# atxmega16d4.net
KiCad netlist of a schematic drawn in EAGLE
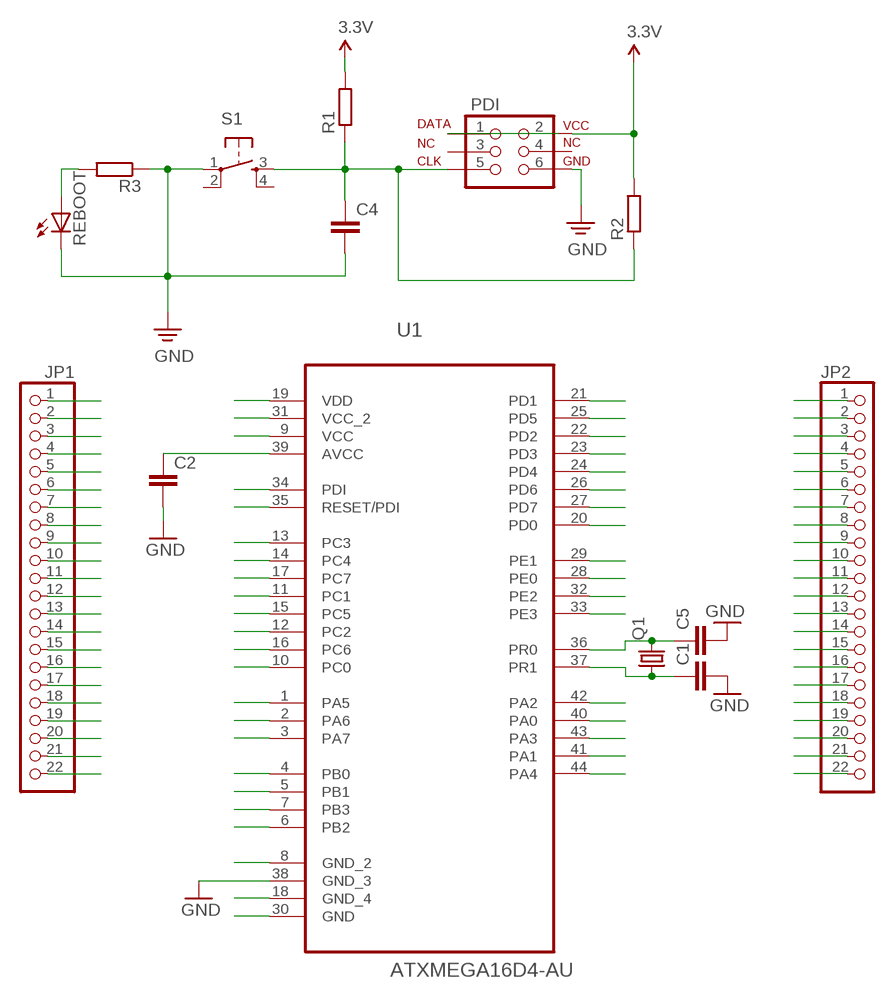
[diagram p0: schematic, sheet 1]

(export (version "E")
  (design (tool "Eeschema 10.0.6"))
  (components
    (comp (ref "C1")
      (value "C-EU025-025X050")
      (footprint "eagle-import:C025-025X050")
      (libsource (lib "eagle-import") (part "C-EU025-025X050"))
    )
    (comp (ref "C2")
      (value "C-EU025-025X050")
      (footprint "eagle-import:C025-025X050")
      (libsource (lib "eagle-import") (part "C-EU025-025X050"))
    )
    (comp (ref "C4")
      (value "C-EU025-040X050")
      (footprint "eagle-import:C025-040X050")
      (libsource (lib "eagle-import") (part "C-EU025-040X050"))
    )
    (comp (ref "C5")
      (value "C-EU025-025X050")
      (footprint "eagle-import:C025-025X050")
      (libsource (lib "eagle-import") (part "C-EU025-025X050"))
    )
    (comp (ref "JP1")
      (value "PINHD-1X22")
      (footprint "eagle-import:1X22")
      (libsource (lib "eagle-import") (part "PINHD-1X22"))
    )
    (comp (ref "JP2")
      (value "PINHD-1X22")
      (footprint "eagle-import:1X22")
      (libsource (lib "eagle-import") (part "PINHD-1X22"))
    )
    (comp (ref "PDI")
      (value "XMEGA_PDI_PRGNS")
      (footprint "eagle-import:2X3-NS")
      (libsource (lib "eagle-import") (part "XMEGA_PDI_PRGNS"))
    )
    (comp (ref "Q1")
      (value "CRYSTALHC49U-V")
      (footprint "eagle-import:HC49U-V")
      (libsource (lib "eagle-import") (part "CRYSTALHC49U-V"))
    )
    (comp (ref "R1")
      (value "R-EU_0309/10")
      (footprint "eagle-import:0309_10")
      (libsource (lib "eagle-import") (part "R-EU_0309/10"))
    )
    (comp (ref "R2")
      (value "R-EU_0207/10")
      (footprint "eagle-import:0207_10")
      (libsource (lib "eagle-import") (part "R-EU_0207/10"))
    )
    (comp (ref "R3")
      (value "R-EU_0207/10")
      (footprint "eagle-import:0207_10")
      (libsource (lib "eagle-import") (part "R-EU_0207/10"))
    )
    (comp (ref "REBOOT")
      (value "LED3MM")
      (footprint "eagle-import:LED3MM")
      (libsource (lib "eagle-import") (part "LED3MM"))
    )
    (comp (ref "S1")
      (value "TAC_SWITCHPTH")
      (footprint "eagle-import:TACTILE-PTH")
      (libsource (lib "eagle-import") (part "TAC_SWITCHPTH"))
    )
    (comp (ref "U1")
      (value "ATXMEGA16D4-AU")
      (footprint "eagle-import:QFP80P1200X1200X120-44N")
      (libsource (lib "eagle-import") (part "ATXMEGA16D4-AU"))
    )
  )
  (nets
    (net (code "1") (name "/PA0") (class "Default")
      (node (ref "JP2") (pin "18") (pinfunction "18_18") (pintype "passive"))
      (node (ref "U1") (pin "40") (pinfunction "PA0_40") (pintype "bidirectional"))
    )
    (net (code "2") (name "/PA1") (class "Default")
      (node (ref "JP2") (pin "19") (pinfunction "19_19") (pintype "passive"))
      (node (ref "U1") (pin "41") (pinfunction "PA1_41") (pintype "bidirectional"))
    )
    (net (code "3") (name "/PA2") (class "Default")
      (node (ref "JP2") (pin "20") (pinfunction "20_20") (pintype "passive"))
      (node (ref "U1") (pin "42") (pinfunction "PA2_42") (pintype "bidirectional"))
    )
    (net (code "4") (name "/PA3") (class "Default")
      (node (ref "JP2") (pin "21") (pinfunction "21_21") (pintype "passive"))
      (node (ref "U1") (pin "43") (pinfunction "PA3_43") (pintype "bidirectional"))
    )
    (net (code "5") (name "/PA4") (class "Default")
      (node (ref "JP2") (pin "22") (pinfunction "22_22") (pintype "passive"))
      (node (ref "U1") (pin "44") (pinfunction "PA4_44") (pintype "bidirectional"))
    )
    (net (code "6") (name "/PA5") (class "Default")
      (node (ref "JP1") (pin "1") (pinfunction "1_1") (pintype "passive"))
      (node (ref "U1") (pin "1") (pinfunction "PA5_1") (pintype "bidirectional"))
    )
    (net (code "7") (name "/PA6") (class "Default")
      (node (ref "JP1") (pin "2") (pinfunction "2_2") (pintype "passive"))
      (node (ref "U1") (pin "2") (pinfunction "PA6_2") (pintype "bidirectional"))
    )
    (net (code "8") (name "/PA7") (class "Default")
      (node (ref "JP1") (pin "3") (pinfunction "3_3") (pintype "passive"))
      (node (ref "U1") (pin "3") (pinfunction "PA7_3") (pintype "bidirectional"))
    )
    (net (code "9") (name "/PB0") (class "Default")
      (node (ref "JP1") (pin "4") (pinfunction "4_4") (pintype "passive"))
      (node (ref "U1") (pin "4") (pinfunction "PB0_4") (pintype "bidirectional"))
    )
    (net (code "10") (name "/PB1") (class "Default")
      (node (ref "JP1") (pin "5") (pinfunction "5_5") (pintype "passive"))
      (node (ref "U1") (pin "5") (pinfunction "PB1_5") (pintype "bidirectional"))
    )
    (net (code "11") (name "/PB2") (class "Default")
      (node (ref "JP1") (pin "6") (pinfunction "6_6") (pintype "passive"))
      (node (ref "U1") (pin "6") (pinfunction "PB2_6") (pintype "bidirectional"))
    )
    (net (code "12") (name "/PB3") (class "Default")
      (node (ref "JP1") (pin "7") (pinfunction "7_7") (pintype "passive"))
      (node (ref "U1") (pin "7") (pinfunction "PB3_7") (pintype "bidirectional"))
    )
    (net (code "13") (name "/PC0") (class "Default")
      (node (ref "JP1") (pin "10") (pinfunction "10_10") (pintype "passive"))
      (node (ref "U1") (pin "10") (pinfunction "PC0_10") (pintype "bidirectional"))
    )
    (net (code "14") (name "/PC1") (class "Default")
      (node (ref "JP1") (pin "11") (pinfunction "11_11") (pintype "passive"))
      (node (ref "U1") (pin "11") (pinfunction "PC1_11") (pintype "bidirectional"))
    )
    (net (code "15") (name "/PC2") (class "Default")
      (node (ref "JP1") (pin "12") (pinfunction "12_12") (pintype "passive"))
      (node (ref "U1") (pin "12") (pinfunction "PC2_12") (pintype "bidirectional"))
    )
    (net (code "16") (name "/PC3") (class "Default")
      (node (ref "JP1") (pin "13") (pinfunction "13_13") (pintype "passive"))
      (node (ref "U1") (pin "13") (pinfunction "PC3_13") (pintype "bidirectional"))
    )
    (net (code "17") (name "/PC4") (class "Default")
      (node (ref "JP1") (pin "14") (pinfunction "14_14") (pintype "passive"))
      (node (ref "U1") (pin "14") (pinfunction "PC4_14") (pintype "bidirectional"))
    )
    (net (code "18") (name "/PC5") (class "Default")
      (node (ref "JP1") (pin "15") (pinfunction "15_15") (pintype "passive"))
      (node (ref "U1") (pin "15") (pinfunction "PC5_15") (pintype "bidirectional"))
    )
    (net (code "19") (name "/PC6") (class "Default")
      (node (ref "JP1") (pin "16") (pinfunction "16_16") (pintype "passive"))
      (node (ref "U1") (pin "16") (pinfunction "PC6_16") (pintype "bidirectional"))
    )
    (net (code "20") (name "/PC7") (class "Default")
      (node (ref "JP1") (pin "17") (pinfunction "17_17") (pintype "passive"))
      (node (ref "U1") (pin "17") (pinfunction "PC7_17") (pintype "bidirectional"))
    )
    (net (code "21") (name "/PD0") (class "Default")
      (node (ref "JP1") (pin "20") (pinfunction "20_20") (pintype "passive"))
      (node (ref "U1") (pin "20") (pinfunction "PD0_20") (pintype "bidirectional"))
    )
    (net (code "22") (name "/PD1") (class "Default")
      (node (ref "JP1") (pin "21") (pinfunction "21_21") (pintype "passive"))
      (node (ref "U1") (pin "21") (pinfunction "PD1_21") (pintype "bidirectional"))
    )
    (net (code "23") (name "/PD2") (class "Default")
      (node (ref "JP1") (pin "22") (pinfunction "22_22") (pintype "passive"))
      (node (ref "U1") (pin "22") (pinfunction "PD2_22") (pintype "bidirectional"))
    )
    (net (code "24") (name "/PD3") (class "Default")
      (node (ref "JP2") (pin "1") (pinfunction "1_1") (pintype "passive"))
      (node (ref "U1") (pin "23") (pinfunction "PD3_23") (pintype "bidirectional"))
    )
    (net (code "25") (name "/PD4") (class "Default")
      (node (ref "JP2") (pin "2") (pinfunction "2_2") (pintype "passive"))
      (node (ref "U1") (pin "24") (pinfunction "PD4_24") (pintype "bidirectional"))
    )
    (net (code "26") (name "/PD5") (class "Default")
      (node (ref "JP2") (pin "3") (pinfunction "3_3") (pintype "passive"))
      (node (ref "U1") (pin "25") (pinfunction "PD5_25") (pintype "bidirectional"))
    )
    (net (code "27") (name "/PD6") (class "Default")
      (node (ref "JP2") (pin "4") (pinfunction "4_4") (pintype "passive"))
      (node (ref "U1") (pin "26") (pinfunction "PD6_26") (pintype "bidirectional"))
    )
    (net (code "28") (name "/PD7") (class "Default")
      (node (ref "JP2") (pin "5") (pinfunction "5_5") (pintype "passive"))
      (node (ref "U1") (pin "27") (pinfunction "PD7_27") (pintype "bidirectional"))
    )
    (net (code "29") (name "/PDI") (class "Default")
      (node (ref "JP2") (pin "12") (pinfunction "12_12") (pintype "passive"))
      (node (ref "PDI") (pin "1") (pinfunction "1_1") (pintype "passive"))
      (node (ref "U1") (pin "34") (pinfunction "PDI_34") (pintype "passive"))
    )
    (net (code "30") (name "/PE0") (class "Default")
      (node (ref "JP2") (pin "6") (pinfunction "6_6") (pintype "passive"))
      (node (ref "U1") (pin "28") (pinfunction "PE0_28") (pintype "bidirectional"))
    )
    (net (code "31") (name "/PE1") (class "Default")
      (node (ref "JP2") (pin "7") (pinfunction "7_7") (pintype "passive"))
      (node (ref "U1") (pin "29") (pinfunction "PE1_29") (pintype "bidirectional"))
    )
    (net (code "32") (name "/PE2") (class "Default")
      (node (ref "JP2") (pin "10") (pinfunction "10_10") (pintype "passive"))
      (node (ref "U1") (pin "32") (pinfunction "PE2_32") (pintype "bidirectional"))
    )
    (net (code "33") (name "/PE3") (class "Default")
      (node (ref "JP2") (pin "11") (pinfunction "11_11") (pintype "passive"))
      (node (ref "U1") (pin "33") (pinfunction "PE3_33") (pintype "bidirectional"))
    )
    (net (code "34") (name "/PR0") (class "Default")
      (node (ref "C5") (pin "1") (pinfunction "1_1") (pintype "passive"))
      (node (ref "JP2") (pin "14") (pinfunction "14_14") (pintype "passive"))
      (node (ref "Q1") (pin "2") (pinfunction "2_2") (pintype "passive"))
      (node (ref "U1") (pin "36") (pinfunction "PR0_36") (pintype "bidirectional"))
    )
    (net (code "35") (name "/PR1") (class "Default")
      (node (ref "C1") (pin "1") (pinfunction "1_1") (pintype "passive"))
      (node (ref "JP2") (pin "15") (pinfunction "15_15") (pintype "passive"))
      (node (ref "Q1") (pin "1") (pinfunction "1_1") (pintype "passive"))
      (node (ref "U1") (pin "37") (pinfunction "PR1_37") (pintype "bidirectional"))
    )
    (net (code "36") (name "/RESET") (class "Default")
      (node (ref "C4") (pin "1") (pinfunction "1_1") (pintype "passive"))
      (node (ref "JP2") (pin "13") (pinfunction "13_13") (pintype "passive"))
      (node (ref "PDI") (pin "5") (pinfunction "5_5") (pintype "passive"))
      (node (ref "R1") (pin "1") (pinfunction "1_1") (pintype "passive"))
      (node (ref "R2") (pin "1") (pinfunction "1_1") (pintype "passive"))
      (node (ref "S1") (pin "3") (pinfunction "3_3") (pintype "passive"))
      (node (ref "U1") (pin "35") (pinfunction "RESET/PDI_35") (pintype "input"))
    )
    (net (code "37") (name "3.3V") (class "Default")
      (node (ref "C2") (pin "1") (pinfunction "1_1") (pintype "passive"))
      (node (ref "JP1") (pin "19") (pinfunction "19_19") (pintype "passive"))
      (node (ref "JP1") (pin "9") (pinfunction "9_9") (pintype "passive"))
      (node (ref "JP2") (pin "17") (pinfunction "17_17") (pintype "passive"))
      (node (ref "JP2") (pin "9") (pinfunction "9_9") (pintype "passive"))
      (node (ref "PDI") (pin "2") (pinfunction "2_2") (pintype "passive"))
      (node (ref "R1") (pin "2") (pinfunction "2_2") (pintype "passive"))
      (node (ref "R2") (pin "2") (pinfunction "2_2") (pintype "passive"))
      (node (ref "U1") (pin "19") (pinfunction "VDD_19") (pintype "power_in"))
      (node (ref "U1") (pin "31") (pinfunction "VCC_2_31") (pintype "power_in"))
      (node (ref "U1") (pin "39") (pinfunction "AVCC_39") (pintype "power_in"))
      (node (ref "U1") (pin "9") (pinfunction "VCC_9") (pintype "power_in"))
    )
    (net (code "38") (name "GND") (class "Default")
      (node (ref "C1") (pin "2") (pinfunction "2_2") (pintype "passive"))
      (node (ref "C2") (pin "2") (pinfunction "2_2") (pintype "passive"))
      (node (ref "C4") (pin "2") (pinfunction "2_2") (pintype "passive"))
      (node (ref "C5") (pin "2") (pinfunction "2_2") (pintype "passive"))
      (node (ref "JP1") (pin "18") (pinfunction "18_18") (pintype "passive"))
      (node (ref "JP1") (pin "8") (pinfunction "8_8") (pintype "passive"))
      (node (ref "JP2") (pin "16") (pinfunction "16_16") (pintype "passive"))
      (node (ref "JP2") (pin "8") (pinfunction "8_8") (pintype "passive"))
      (node (ref "PDI") (pin "6") (pinfunction "6_6") (pintype "passive"))
      (node (ref "R3") (pin "1") (pinfunction "1_1") (pintype "passive"))
      (node (ref "REBOOT") (pin "K") (pinfunction "C_K") (pintype "passive"))
      (node (ref "S1") (pin "1") (pinfunction "1_1") (pintype "passive"))
      (node (ref "U1") (pin "18") (pinfunction "GND_4_18") (pintype "passive"))
      (node (ref "U1") (pin "30") (pinfunction "GND_30") (pintype "passive"))
      (node (ref "U1") (pin "38") (pinfunction "GND_3_38") (pintype "passive"))
      (node (ref "U1") (pin "8") (pinfunction "GND_2_8") (pintype "passive"))
    )
    (net (code "39") (name "Net-(R3-Pad2)") (class "Default")
      (node (ref "R3") (pin "2") (pinfunction "2_2") (pintype "passive"))
      (node (ref "REBOOT") (pin "A") (pinfunction "A_A") (pintype "passive"))
    )
    (net (code "40") (name "unconnected-(PDI-Pad3)") (class "Default")
      (node (ref "PDI") (pin "3") (pinfunction "3_3") (pintype "passive"))
    )
    (net (code "41") (name "unconnected-(PDI-Pad4)") (class "Default")
      (node (ref "PDI") (pin "4") (pinfunction "4_4") (pintype "passive"))
    )
    (net (code "42") (name "unconnected-(S1-Pad2)") (class "Default")
      (node (ref "S1") (pin "2") (pinfunction "2_2") (pintype "passive"))
    )
    (net (code "43") (name "unconnected-(S1-Pad4)") (class "Default")
      (node (ref "S1") (pin "4") (pinfunction "4_4") (pintype "passive"))
    )
  )
)
